# LCRBoard.net
KiCad netlist of a schematic drawn in Altium Designer
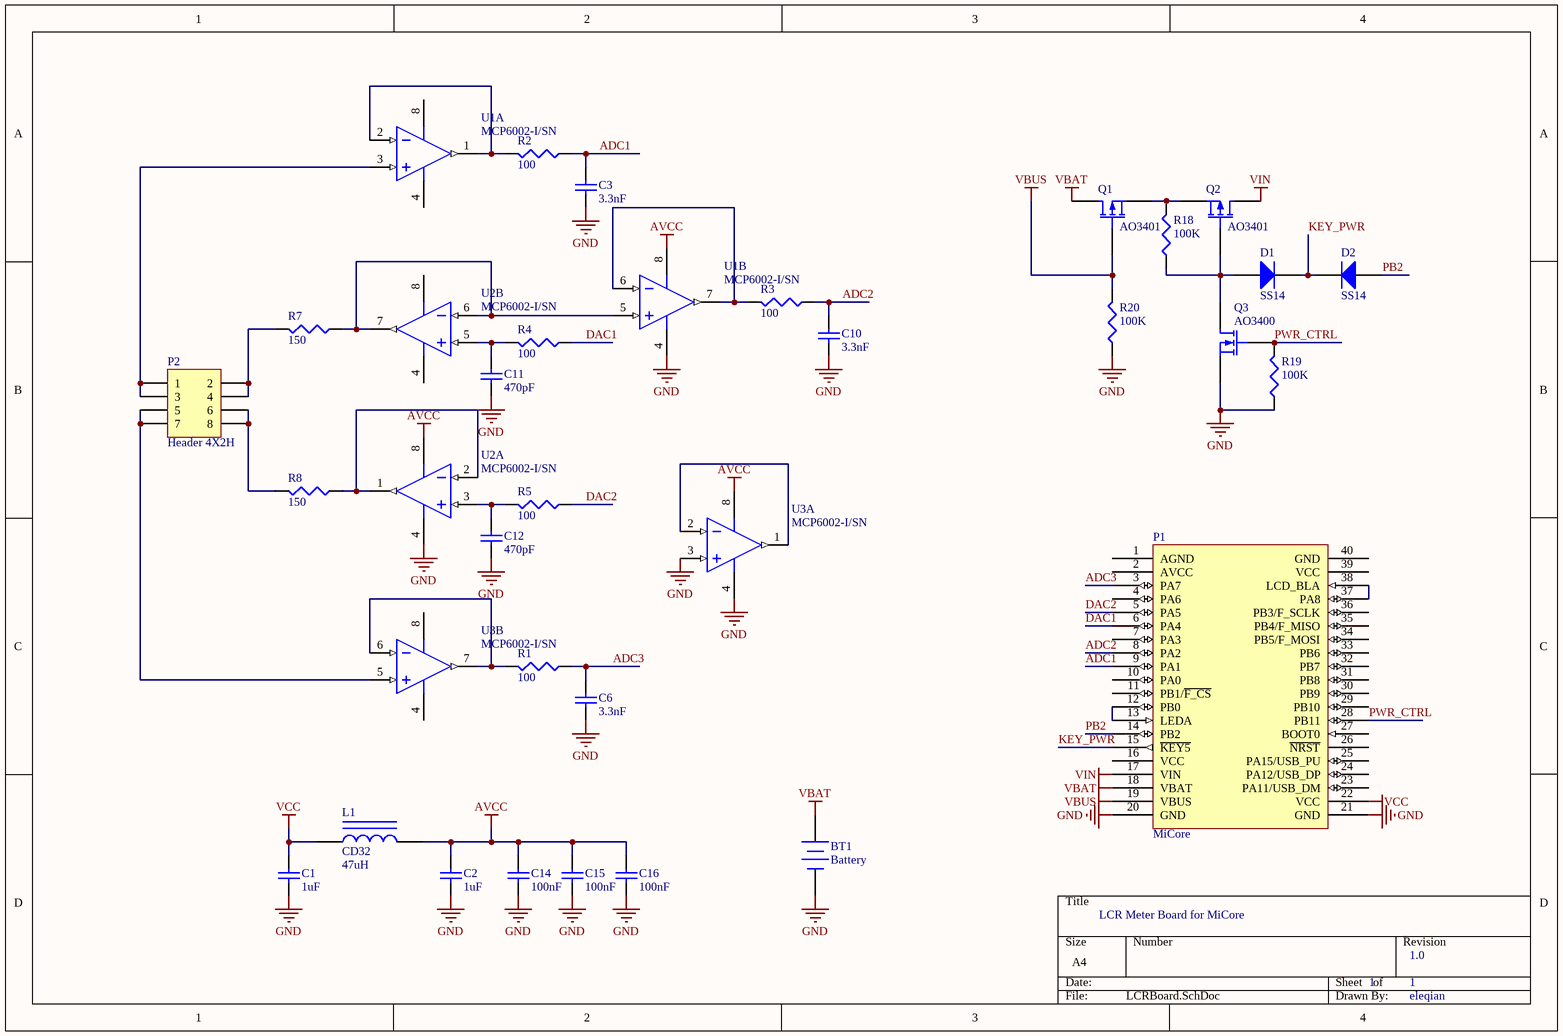
[diagram p0: LCRBoard.SchDoc]

(export (version "E")
  (design (tool "Eeschema 10.0.6"))
  (components
    (comp (ref "BT1")
      (value "Battery")
      (footprint "BAT-2")
      (description "Multicell Battery")
      (fields (field (name "PUBLISHER") "Altium Limited"))
      (libsource (lib "Miscellaneous Devices") (part "Battery"))
    )
    (comp (ref "C1")
      (value "1uF")
      (footprint "0603C")
      (description "Capacitor")
      (fields (field (name "Comment") "Cap") (field (name "PUBLISHER") "Altium Limited"))
      (libsource (lib "Miscellaneous Devices") (part "Cap"))
    )
    (comp (ref "C2")
      (value "1uF")
      (footprint "0603C")
      (description "Capacitor")
      (fields (field (name "Comment") "Cap") (field (name "PUBLISHER") "Altium Limited"))
      (libsource (lib "Miscellaneous Devices") (part "Cap"))
    )
    (comp (ref "C3")
      (value "3.3nF")
      (footprint "0603C")
      (description "Capacitor")
      (fields (field (name "Comment") "Cap") (field (name "PUBLISHER") "Altium Limited"))
      (libsource (lib "Miscellaneous Devices") (part "Cap"))
    )
    (comp (ref "C6")
      (value "3.3nF")
      (footprint "0603C")
      (description "Capacitor")
      (fields (field (name "Comment") "Cap") (field (name "PUBLISHER") "Altium Limited"))
      (libsource (lib "Miscellaneous Devices") (part "Cap"))
    )
    (comp (ref "C10")
      (value "3.3nF")
      (footprint "0603C")
      (description "Capacitor")
      (fields (field (name "Comment") "Cap") (field (name "PUBLISHER") "Altium Limited"))
      (libsource (lib "Miscellaneous Devices") (part "Cap"))
    )
    (comp (ref "C11")
      (value "470pF")
      (footprint "0603C")
      (description "Capacitor")
      (fields (field (name "Comment") "Cap") (field (name "PUBLISHER") "Altium Limited"))
      (libsource (lib "Miscellaneous Devices") (part "Cap"))
    )
    (comp (ref "C12")
      (value "470pF")
      (footprint "0603C")
      (description "Capacitor")
      (fields (field (name "Comment") "Cap") (field (name "PUBLISHER") "Altium Limited"))
      (libsource (lib "Miscellaneous Devices") (part "Cap"))
    )
    (comp (ref "C14")
      (value "100nF")
      (footprint "0603C")
      (description "Capacitor")
      (fields (field (name "Comment") "Cap") (field (name "PUBLISHER") "Altium Limited"))
      (libsource (lib "Miscellaneous Devices") (part "Cap"))
    )
    (comp (ref "C15")
      (value "100nF")
      (footprint "0603C")
      (description "Capacitor")
      (fields (field (name "Comment") "Cap") (field (name "PUBLISHER") "Altium Limited"))
      (libsource (lib "Miscellaneous Devices") (part "Cap"))
    )
    (comp (ref "C16")
      (value "100nF")
      (footprint "0603C")
      (description "Capacitor")
      (fields (field (name "Comment") "Cap") (field (name "PUBLISHER") "Altium Limited"))
      (libsource (lib "Miscellaneous Devices") (part "Cap"))
    )
    (comp (ref "D1")
      (value "SS14")
      (footprint "0805D")
      (description "Default Diode")
      (fields (field (name "PUBLISHER") "Altium Limited"))
      (libsource (lib "Miscellaneous Devices") (part "Diode"))
    )
    (comp (ref "D2")
      (value "SS14")
      (footprint "0805D")
      (description "Default Diode")
      (fields (field (name "PUBLISHER") "Altium Limited"))
      (libsource (lib "Miscellaneous Devices") (part "Diode"))
    )
    (comp (ref "L1")
      (value "CD32")
      (footprint "CD32")
      (description "Magnetic-Core Inductor")
      (fields (field (name "ALTIUM_VALUE") "47uH") (field (name "PUBLISHER") "Altium Limited"))
      (libsource (lib "Miscellaneous Devices") (part "Inductor Iron"))
    )
    (comp (ref "P1") (value "MiCore") (description "MiCore核心板") (libsource (lib "MiCore") (part "MiCore")))
    (comp (ref "P2")
      (value "Header 4X2H")
      (footprint "HDR2X4H")
      (description "Header, 4-Pin, Dual row, Right Angle")
      (fields (field (name "PUBLISHER") "Altium Limited"))
      (libsource (lib "Miscellaneous Connectors") (part "Header 4X2H"))
    )
    (comp (ref "Q1")
      (value "AO3401")
      (footprint "SOT-23")
      (description "P-Channel MOSFET")
      (fields (field (name "PUBLISHER") "Altium Limited"))
      (libsource (lib "Miscellaneous Devices") (part "MOSFET-P"))
    )
    (comp (ref "Q2")
      (value "AO3401")
      (footprint "SOT-23")
      (description "P-Channel MOSFET")
      (fields (field (name "PUBLISHER") "Altium Limited"))
      (libsource (lib "Miscellaneous Devices") (part "MOSFET-P"))
    )
    (comp (ref "Q3")
      (value "AO3400")
      (footprint "SOT-23")
      (description "N-Channel MOSFET")
      (fields (field (name "PUBLISHER") "Altium Limited"))
      (libsource (lib "Miscellaneous Devices") (part "MOSFET-N"))
    )
    (comp (ref "R1")
      (value "100")
      (footprint "0603R")
      (description "Resistor")
      (fields (field (name "Comment") "Res3") (field (name "PUBLISHER") "Altium Limited"))
      (libsource (lib "Miscellaneous Devices") (part "Res3"))
    )
    (comp (ref "R2")
      (value "100")
      (footprint "0603R")
      (description "Resistor")
      (fields (field (name "Comment") "Res3") (field (name "PUBLISHER") "Altium Limited"))
      (libsource (lib "Miscellaneous Devices") (part "Res3"))
    )
    (comp (ref "R3")
      (value "100")
      (footprint "0603R")
      (description "Resistor")
      (fields (field (name "Comment") "Res3") (field (name "PUBLISHER") "Altium Limited"))
      (libsource (lib "Miscellaneous Devices") (part "Res3"))
    )
    (comp (ref "R4")
      (value "100")
      (footprint "0603R")
      (description "Resistor")
      (fields (field (name "Comment") "Res3") (field (name "PUBLISHER") "Altium Limited"))
      (libsource (lib "Miscellaneous Devices") (part "Res3"))
    )
    (comp (ref "R5")
      (value "100")
      (footprint "0603R")
      (description "Resistor")
      (fields (field (name "Comment") "Res3") (field (name "PUBLISHER") "Altium Limited"))
      (libsource (lib "Miscellaneous Devices") (part "Res3"))
    )
    (comp (ref "R7")
      (value "150")
      (footprint "0603R")
      (description "Resistor")
      (fields (field (name "Comment") "Res3") (field (name "PUBLISHER") "Altium Limited"))
      (libsource (lib "Miscellaneous Devices") (part "Res3"))
    )
    (comp (ref "R8")
      (value "150")
      (footprint "0603R")
      (description "Resistor")
      (fields (field (name "Comment") "Res3") (field (name "PUBLISHER") "Altium Limited"))
      (libsource (lib "Miscellaneous Devices") (part "Res3"))
    )
    (comp (ref "R18")
      (value "100K")
      (footprint "0603R")
      (description "Resistor")
      (fields (field (name "Comment") "Res3") (field (name "PUBLISHER") "Altium Limited"))
      (libsource (lib "Miscellaneous Devices") (part "Res3"))
    )
    (comp (ref "R19")
      (value "100K")
      (footprint "0603R")
      (description "Resistor")
      (fields (field (name "Comment") "Res3") (field (name "PUBLISHER") "Altium Limited"))
      (libsource (lib "Miscellaneous Devices") (part "Res3"))
    )
    (comp (ref "R20")
      (value "100K")
      (footprint "0603R")
      (description "Resistor")
      (fields (field (name "Comment") "Res3") (field (name "PUBLISHER") "Altium Limited"))
      (libsource (lib "Miscellaneous Devices") (part "Res3"))
    )
    (comp (ref "U1")
      (value "MCP6002-I/SN")
      (footprint "SOIC-SN8_N")
      (description "1 MHz, Low-Power Operational Amplifier, 8-Pin SOIC, Industrial Temperature")
      (fields (field (name "PUBLISHER") "Altium Limited"))
      (libsource (lib "Microchip Linear Devices") (part "MCP6002-I/SN"))
    )
    (comp (ref "U2")
      (value "MCP6002-I/SN")
      (footprint "SOIC-SN8_N")
      (description "1 MHz, Low-Power Operational Amplifier, 8-Pin SOIC, Industrial Temperature")
      (fields (field (name "PUBLISHER") "Altium Limited"))
      (libsource (lib "Microchip Linear Devices") (part "MCP6002-I/SN"))
    )
    (comp (ref "U3")
      (value "MCP6002-I/SN")
      (footprint "SOIC-SN8_N")
      (description "1 MHz, Low-Power Operational Amplifier, 8-Pin SOIC, Industrial Temperature")
      (fields (field (name "PUBLISHER") "Altium Limited"))
      (libsource (lib "Microchip Linear Devices") (part "MCP6002-I/SN"))
    )
  )
  (nets
    (net (code "1") (name "/ADC1") (class "Default")
      (node (ref "C3") (pin "1") (pinfunction "1_1") (pintype "passive"))
      (node (ref "P1") (pin "9") (pinfunction "PA1_9") (pintype "bidirectional"))
      (node (ref "R2") (pin "1") (pinfunction "1_1") (pintype "passive"))
    )
    (net (code "2") (name "/ADC2") (class "Default")
      (node (ref "C10") (pin "1") (pinfunction "1_1") (pintype "passive"))
      (node (ref "P1") (pin "8") (pinfunction "PA2_8") (pintype "bidirectional"))
      (node (ref "R3") (pin "1") (pinfunction "1_1") (pintype "passive"))
    )
    (net (code "3") (name "/ADC3") (class "Default")
      (node (ref "C6") (pin "1") (pinfunction "1_1") (pintype "passive"))
      (node (ref "P1") (pin "3") (pinfunction "PA7_3") (pintype "bidirectional"))
      (node (ref "R1") (pin "1") (pinfunction "1_1") (pintype "passive"))
    )
    (net (code "4") (name "/DAC1") (class "Default")
      (node (ref "P1") (pin "6") (pinfunction "PA4_6") (pintype "bidirectional"))
      (node (ref "R4") (pin "1") (pinfunction "1_1") (pintype "passive"))
    )
    (net (code "5") (name "/DAC2") (class "Default")
      (node (ref "P1") (pin "5") (pinfunction "PA5_5") (pintype "bidirectional"))
      (node (ref "R5") (pin "1") (pinfunction "1_1") (pintype "passive"))
    )
    (net (code "6") (name "/KEY_PWR") (class "Default")
      (node (ref "D1") (pin "2") (pinfunction "K_2") (pintype "passive"))
      (node (ref "D2") (pin "2") (pinfunction "K_2") (pintype "passive"))
      (node (ref "P1") (pin "15") (pinfunction "~{KEY5}_15") (pintype "output"))
    )
    (net (code "7") (name "/PB2") (class "Default")
      (node (ref "D2") (pin "1") (pinfunction "A_1") (pintype "passive"))
      (node (ref "P1") (pin "14") (pinfunction "PB2_14") (pintype "bidirectional"))
    )
    (net (code "8") (name "/PWR_CTRL") (class "Default")
      (node (ref "P1") (pin "28") (pinfunction "PB11_28") (pintype "bidirectional"))
      (node (ref "Q3") (pin "2") (pinfunction "G_2") (pintype "passive"))
      (node (ref "R19") (pin "2") (pinfunction "2_2") (pintype "passive"))
    )
    (net (code "9") (name "AVCC") (class "Default")
      (node (ref "C14") (pin "2") (pinfunction "2_2") (pintype "passive"))
      (node (ref "C15") (pin "2") (pinfunction "2_2") (pintype "passive"))
      (node (ref "C16") (pin "2") (pinfunction "2_2") (pintype "passive"))
      (node (ref "C2") (pin "2") (pinfunction "2_2") (pintype "passive"))
      (node (ref "L1") (pin "2") (pinfunction "2_2") (pintype "passive"))
      (node (ref "U1") (pin "8") (pinfunction "VDD_8") (pintype "power_in"))
      (node (ref "U2") (pin "8") (pinfunction "VDD_8") (pintype "power_in"))
      (node (ref "U3") (pin "8") (pinfunction "VDD_8") (pintype "power_in"))
    )
    (net (code "10") (name "GND") (class "Default")
      (node (ref "BT1") (pin "2") (pinfunction "-_2") (pintype "passive"))
      (node (ref "C1") (pin "1") (pinfunction "1_1") (pintype "passive"))
      (node (ref "C10") (pin "2") (pinfunction "2_2") (pintype "passive"))
      (node (ref "C11") (pin "2") (pinfunction "2_2") (pintype "passive"))
      (node (ref "C12") (pin "2") (pinfunction "2_2") (pintype "passive"))
      (node (ref "C14") (pin "1") (pinfunction "1_1") (pintype "passive"))
      (node (ref "C15") (pin "1") (pinfunction "1_1") (pintype "passive"))
      (node (ref "C16") (pin "1") (pinfunction "1_1") (pintype "passive"))
      (node (ref "C2") (pin "1") (pinfunction "1_1") (pintype "passive"))
      (node (ref "C3") (pin "2") (pinfunction "2_2") (pintype "passive"))
      (node (ref "C6") (pin "2") (pinfunction "2_2") (pintype "passive"))
      (node (ref "P1") (pin "20") (pinfunction "GND_20") (pintype "power_in"))
      (node (ref "P1") (pin "21") (pinfunction "GND_21") (pintype "power_in"))
      (node (ref "Q3") (pin "3") (pinfunction "S_3") (pintype "passive"))
      (node (ref "R19") (pin "1") (pinfunction "1_1") (pintype "passive"))
      (node (ref "R20") (pin "1") (pinfunction "1_1") (pintype "passive"))
      (node (ref "U1") (pin "4") (pinfunction "VSS_4") (pintype "power_in"))
      (node (ref "U2") (pin "4") (pinfunction "VSS_4") (pintype "power_in"))
      (node (ref "U3") (pin "3") (pinfunction "VINA+_3") (pintype "input"))
      (node (ref "U3") (pin "4") (pinfunction "VSS_4") (pintype "power_in"))
    )
    (net (code "11") (name "Net-(D1-A)") (class "Default")
      (node (ref "D1") (pin "1") (pinfunction "A_1") (pintype "passive"))
      (node (ref "Q2") (pin "2") (pinfunction "G_2") (pintype "passive"))
      (node (ref "Q3") (pin "1") (pinfunction "D_1") (pintype "passive"))
      (node (ref "R18") (pin "1") (pinfunction "1_1") (pintype "passive"))
    )
    (net (code "12") (name "Net-(P1-LCD_BLA)") (class "Default")
      (node (ref "P1") (pin "37") (pinfunction "PA8_37") (pintype "bidirectional"))
      (node (ref "P1") (pin "38") (pinfunction "LCD_BLA_38") (pintype "input"))
    )
    (net (code "13") (name "Net-(P1-LEDA)") (class "Default")
      (node (ref "P1") (pin "12") (pinfunction "PB0_12") (pintype "bidirectional"))
      (node (ref "P1") (pin "13") (pinfunction "LEDA_13") (pintype "input"))
    )
    (net (code "14") (name "Net-(P2-Pad2)") (class "Default")
      (node (ref "P2") (pin "2") (pinfunction "2_2") (pintype "passive"))
      (node (ref "P2") (pin "4") (pinfunction "4_4") (pintype "passive"))
      (node (ref "R7") (pin "2") (pinfunction "2_2") (pintype "passive"))
    )
    (net (code "15") (name "Net-(P2-Pad6)") (class "Default")
      (node (ref "P2") (pin "6") (pinfunction "6_6") (pintype "passive"))
      (node (ref "P2") (pin "8") (pinfunction "8_8") (pintype "passive"))
      (node (ref "R8") (pin "2") (pinfunction "2_2") (pintype "passive"))
    )
    (net (code "16") (name "Net-(Q1-S)") (class "Default")
      (node (ref "Q1") (pin "3") (pinfunction "S_3") (pintype "passive"))
      (node (ref "Q2") (pin "3") (pinfunction "S_3") (pintype "passive"))
      (node (ref "R18") (pin "2") (pinfunction "2_2") (pintype "passive"))
    )
    (net (code "17") (name "Net-(U1A-VINA+)") (class "Default")
      (node (ref "P2") (pin "1") (pinfunction "1_1") (pintype "passive"))
      (node (ref "P2") (pin "3") (pinfunction "3_3") (pintype "passive"))
      (node (ref "U1") (pin "3") (pinfunction "VINA+_3") (pintype "input"))
    )
    (net (code "18") (name "Net-(U1A-VINA-)") (class "Default")
      (node (ref "R2") (pin "2") (pinfunction "2_2") (pintype "passive"))
      (node (ref "U1") (pin "1") (pinfunction "VOUTA_1") (pintype "output"))
      (node (ref "U1") (pin "2") (pinfunction "VINA-_2") (pintype "input"))
    )
    (net (code "19") (name "Net-(U1B-VINB+)") (class "Default")
      (node (ref "R7") (pin "1") (pinfunction "1_1") (pintype "passive"))
      (node (ref "U1") (pin "5") (pinfunction "VINB+_5") (pintype "input"))
      (node (ref "U2") (pin "6") (pinfunction "VINB-_6") (pintype "input"))
      (node (ref "U2") (pin "7") (pinfunction "VOUTB_7") (pintype "output"))
    )
    (net (code "20") (name "Net-(U1B-VINB-)") (class "Default")
      (node (ref "R3") (pin "2") (pinfunction "2_2") (pintype "passive"))
      (node (ref "U1") (pin "6") (pinfunction "VINB-_6") (pintype "input"))
      (node (ref "U1") (pin "7") (pinfunction "VOUTB_7") (pintype "output"))
    )
    (net (code "21") (name "Net-(U2A-VINA+)") (class "Default")
      (node (ref "C12") (pin "1") (pinfunction "1_1") (pintype "passive"))
      (node (ref "R5") (pin "2") (pinfunction "2_2") (pintype "passive"))
      (node (ref "U2") (pin "3") (pinfunction "VINA+_3") (pintype "input"))
    )
    (net (code "22") (name "Net-(U2A-VINA-)") (class "Default")
      (node (ref "R8") (pin "1") (pinfunction "1_1") (pintype "passive"))
      (node (ref "U2") (pin "1") (pinfunction "VOUTA_1") (pintype "output"))
      (node (ref "U2") (pin "2") (pinfunction "VINA-_2") (pintype "input"))
    )
    (net (code "23") (name "Net-(U2B-VINB+)") (class "Default")
      (node (ref "C11") (pin "1") (pinfunction "1_1") (pintype "passive"))
      (node (ref "R4") (pin "2") (pinfunction "2_2") (pintype "passive"))
      (node (ref "U2") (pin "5") (pinfunction "VINB+_5") (pintype "input"))
    )
    (net (code "24") (name "Net-(U3A-VINA-)") (class "Default")
      (node (ref "U3") (pin "1") (pinfunction "VOUTA_1") (pintype "output"))
      (node (ref "U3") (pin "2") (pinfunction "VINA-_2") (pintype "input"))
    )
    (net (code "25") (name "Net-(U3B-VINB+)") (class "Default")
      (node (ref "P2") (pin "5") (pinfunction "5_5") (pintype "passive"))
      (node (ref "P2") (pin "7") (pinfunction "7_7") (pintype "passive"))
      (node (ref "U3") (pin "5") (pinfunction "VINB+_5") (pintype "input"))
    )
    (net (code "26") (name "Net-(U3B-VINB-)") (class "Default")
      (node (ref "R1") (pin "2") (pinfunction "2_2") (pintype "passive"))
      (node (ref "U3") (pin "6") (pinfunction "VINB-_6") (pintype "input"))
      (node (ref "U3") (pin "7") (pinfunction "VOUTB_7") (pintype "output"))
    )
    (net (code "27") (name "VBAT") (class "Default")
      (node (ref "BT1") (pin "1") (pinfunction "+_1") (pintype "passive"))
      (node (ref "P1") (pin "18") (pinfunction "VBAT_18") (pintype "power_in"))
      (node (ref "Q1") (pin "1") (pinfunction "D_1") (pintype "passive"))
    )
    (net (code "28") (name "VBUS") (class "Default")
      (node (ref "P1") (pin "19") (pinfunction "VBUS_19") (pintype "power_in"))
      (node (ref "Q1") (pin "2") (pinfunction "G_2") (pintype "passive"))
      (node (ref "R20") (pin "2") (pinfunction "2_2") (pintype "passive"))
    )
    (net (code "29") (name "VCC") (class "Default")
      (node (ref "C1") (pin "2") (pinfunction "2_2") (pintype "passive"))
      (node (ref "L1") (pin "1") (pinfunction "1_1") (pintype "passive"))
      (node (ref "P1") (pin "22") (pinfunction "VCC_22") (pintype "power_in"))
    )
    (net (code "30") (name "VIN") (class "Default")
      (node (ref "P1") (pin "17") (pinfunction "VIN_17") (pintype "power_in"))
      (node (ref "Q2") (pin "1") (pinfunction "D_1") (pintype "passive"))
    )
    (net (code "31") (name "unconnected-(P1-AGND-Pad1)") (class "Default")
      (node (ref "P1") (pin "1") (pinfunction "AGND_1") (pintype "power_in"))
    )
    (net (code "32") (name "unconnected-(P1-AVCC-Pad2)") (class "Default")
      (node (ref "P1") (pin "2") (pinfunction "AVCC_2") (pintype "power_in"))
    )
    (net (code "33") (name "unconnected-(P1-BOOT0-Pad27)") (class "Default")
      (node (ref "P1") (pin "27") (pinfunction "BOOT0_27") (pintype "input"))
    )
    (net (code "34") (name "unconnected-(P1-GND-Pad40)") (class "Default")
      (node (ref "P1") (pin "40") (pinfunction "GND_40") (pintype "power_in"))
    )
    (net (code "35") (name "unconnected-(P1-PA0-Pad10)") (class "Default")
      (node (ref "P1") (pin "10") (pinfunction "PA0_10") (pintype "bidirectional"))
    )
    (net (code "36") (name "unconnected-(P1-PA3-Pad7)") (class "Default")
      (node (ref "P1") (pin "7") (pinfunction "PA3_7") (pintype "bidirectional"))
    )
    (net (code "37") (name "unconnected-(P1-PA6-Pad4)") (class "Default")
      (node (ref "P1") (pin "4") (pinfunction "PA6_4") (pintype "bidirectional"))
    )
    (net (code "38") (name "unconnected-(P1-PA11{slash}USB_DM-Pad23)") (class "Default")
      (node (ref "P1") (pin "23") (pinfunction "PA11/USB_DM_23") (pintype "bidirectional"))
    )
    (net (code "39") (name "unconnected-(P1-PA12{slash}USB_DP-Pad24)") (class "Default")
      (node (ref "P1") (pin "24") (pinfunction "PA12/USB_DP_24") (pintype "bidirectional"))
    )
    (net (code "40") (name "unconnected-(P1-PA15{slash}USB_PU-Pad25)") (class "Default")
      (node (ref "P1") (pin "25") (pinfunction "PA15/USB_PU_25") (pintype "bidirectional"))
    )
    (net (code "41") (name "unconnected-(P1-PB1{slash}~{F_CS}-Pad11)") (class "Default")
      (node (ref "P1") (pin "11") (pinfunction "PB1/~{F_CS}_11") (pintype "bidirectional"))
    )
    (net (code "42") (name "unconnected-(P1-PB3{slash}F_SCLK-Pad36)") (class "Default")
      (node (ref "P1") (pin "36") (pinfunction "PB3/F_SCLK_36") (pintype "bidirectional"))
    )
    (net (code "43") (name "unconnected-(P1-PB4{slash}F_MISO-Pad35)") (class "Default")
      (node (ref "P1") (pin "35") (pinfunction "PB4/F_MISO_35") (pintype "bidirectional"))
    )
    (net (code "44") (name "unconnected-(P1-PB5{slash}F_MOSI-Pad34)") (class "Default")
      (node (ref "P1") (pin "34") (pinfunction "PB5/F_MOSI_34") (pintype "bidirectional"))
    )
    (net (code "45") (name "unconnected-(P1-PB6-Pad33)") (class "Default")
      (node (ref "P1") (pin "33") (pinfunction "PB6_33") (pintype "bidirectional"))
    )
    (net (code "46") (name "unconnected-(P1-PB7-Pad32)") (class "Default")
      (node (ref "P1") (pin "32") (pinfunction "PB7_32") (pintype "bidirectional"))
    )
    (net (code "47") (name "unconnected-(P1-PB8-Pad31)") (class "Default")
      (node (ref "P1") (pin "31") (pinfunction "PB8_31") (pintype "bidirectional"))
    )
    (net (code "48") (name "unconnected-(P1-PB9-Pad30)") (class "Default")
      (node (ref "P1") (pin "30") (pinfunction "PB9_30") (pintype "bidirectional"))
    )
    (net (code "49") (name "unconnected-(P1-PB10-Pad29)") (class "Default")
      (node (ref "P1") (pin "29") (pinfunction "PB10_29") (pintype "bidirectional"))
    )
    (net (code "50") (name "unconnected-(P1-VCC-Pad16)") (class "Default")
      (node (ref "P1") (pin "16") (pinfunction "VCC_16") (pintype "power_in"))
    )
    (net (code "51") (name "unconnected-(P1-VCC-Pad39)") (class "Default")
      (node (ref "P1") (pin "39") (pinfunction "VCC_39") (pintype "power_in"))
    )
    (net (code "52") (name "unconnected-(P1-~{NRST}-Pad26)") (class "Default")
      (node (ref "P1") (pin "26") (pinfunction "~{NRST}_26") (pintype "open_collector"))
    )
    (net (code "53") (name "unconnected-(U1A-VDD-Pad8)") (class "Default")
      (node (ref "U1") (pin "8") (pinfunction "VDD_8") (pintype "power_in"))
    )
    (net (code "54") (name "unconnected-(U1A-VSS-Pad4)") (class "Default")
      (node (ref "U1") (pin "4") (pinfunction "VSS_4") (pintype "power_in"))
    )
    (net (code "55") (name "unconnected-(U2B-VDD-Pad8)") (class "Default")
      (node (ref "U2") (pin "8") (pinfunction "VDD_8") (pintype "power_in"))
    )
    (net (code "56") (name "unconnected-(U2B-VSS-Pad4)") (class "Default")
      (node (ref "U2") (pin "4") (pinfunction "VSS_4") (pintype "power_in"))
    )
    (net (code "57") (name "unconnected-(U3B-VDD-Pad8)") (class "Default")
      (node (ref "U3") (pin "8") (pinfunction "VDD_8") (pintype "power_in"))
    )
    (net (code "58") (name "unconnected-(U3B-VSS-Pad4)") (class "Default")
      (node (ref "U3") (pin "4") (pinfunction "VSS_4") (pintype "power_in"))
    )
  )
)
